# Switches.net
KiCad netlist of a schematic drawn in Altium Designer
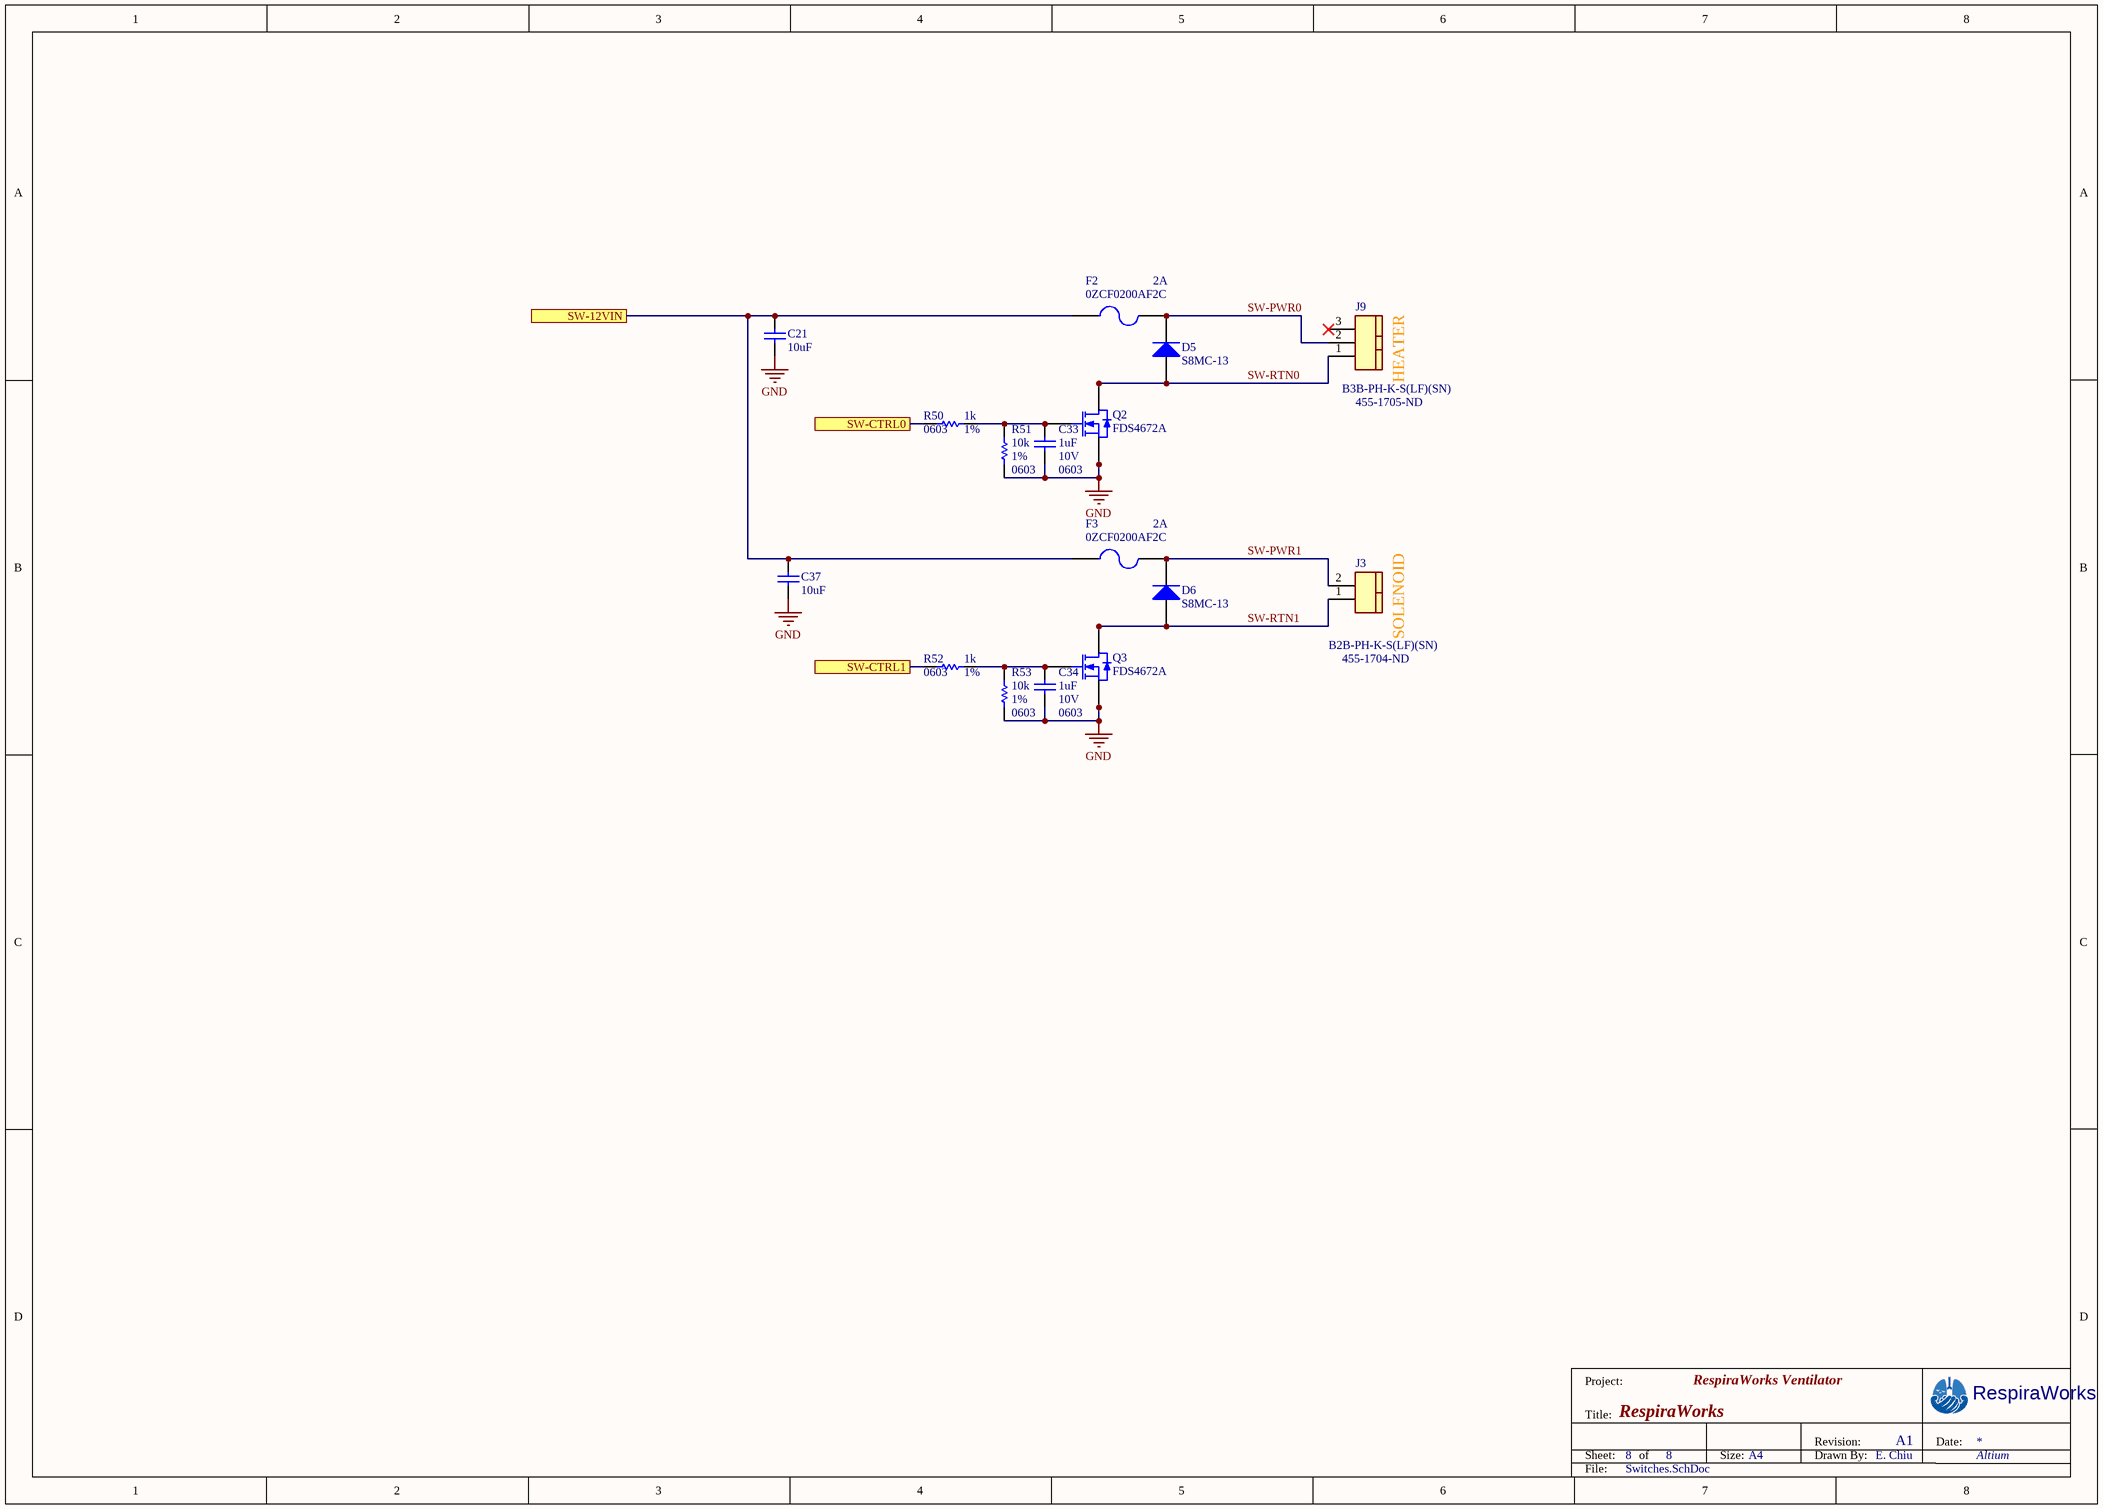
[diagram p0: Switches.SchDoc]

(export (version "E")
  (design (tool "Eeschema 10.0.6"))
  (components
    (comp (ref "C21")
      (value "10uF")
      (footprint "CAP1210")
      (description "Cap 1210")
      (fields (field (name "MANUFACTURER") "Murata") (field (name "VOLTAGE") "25V"))
      (libsource (lib "generic") (part "CAP 1210"))
    )
    (comp (ref "C33")
      (value "1uF")
      (footprint "CAP0603")
      (description "Cap 0603")
      (fields
        (field (name "MANUFACTURER") "Yageo")
        (field (name "VOLTAGE") "10V")
        (field (name "PCB PACKAGE") "0603")
        (field (name "Comment") "CAP 0603")
      )
      (libsource (lib "generic") (part "CAP 0603"))
    )
    (comp (ref "C34")
      (value "1uF")
      (footprint "CAP0603")
      (description "Cap 0603")
      (fields
        (field (name "MANUFACTURER") "Yageo")
        (field (name "VOLTAGE") "10V")
        (field (name "PCB PACKAGE") "0603")
        (field (name "Comment") "CAP 0603")
      )
      (libsource (lib "generic") (part "CAP 0603"))
    )
    (comp (ref "C37")
      (value "10uF")
      (footprint "CAP1210")
      (description "Cap 1210")
      (fields (field (name "MANUFACTURER") "Murata") (field (name "VOLTAGE") "25V"))
      (libsource (lib "generic") (part "CAP 1210"))
    )
    (comp (ref "D5")
      (value "S8MC-13")
      (footprint "DO-214AC")
      (description "Ultra-Fast Signal Diode, Silicon, 100V, 300mA")
      (fields (field (name "MANUFACTURER") "Diodes Inc.") (field (name "MANUFACTURER P/N") "S8MC-13"))
      (libsource (lib "diodes-inc") (part "S8MC-13"))
    )
    (comp (ref "D6")
      (value "S8MC-13")
      (footprint "DO-214AC")
      (description "Ultra-Fast Signal Diode, Silicon, 100V, 300mA")
      (fields (field (name "MANUFACTURER") "Diodes Inc.") (field (name "MANUFACTURER P/N") "S8MC-13"))
      (libsource (lib "diodes-inc") (part "S8MC-13"))
    )
    (comp (ref "F2")
      (value "0ZCF0200AF2C")
      (footprint "FUSE2920")
      (description "PTC Fuse, 2A Hold, 24V, 2920 size")
      (fields
        (field (name "MANUFACTURER P/N") "0ZCF0200AF2C")
        (field (name "MANUFACTURER") "Belfuse")
        (field (name "I(HOLD)") "2A")
      )
      (libsource (lib "belfuse") (part "0ZCF0200AF2C"))
    )
    (comp (ref "F3")
      (value "0ZCF0200AF2C")
      (footprint "FUSE2920")
      (description "PTC Fuse, 2A Hold, 24V, 2920 size")
      (fields
        (field (name "MANUFACTURER P/N") "0ZCF0200AF2C")
        (field (name "MANUFACTURER") "Belfuse")
        (field (name "I(HOLD)") "2A")
      )
      (libsource (lib "belfuse") (part "0ZCF0200AF2C"))
    )
    (comp (ref "J3")
      (value "B2B-PH-K-S(LF)(SN)")
      (footprint "JST_B2B-XH-AM")
      (description "CONN HEADER PH TOP 2POS 2MM")
      (fields
        (field (name "MANUFACTURER") "JST Sales America Inc.")
        (field (name "SUPPLIER PART NUMBER 1") "455-1704-ND")
      )
      (libsource (lib "JST XH") (part "B2B-PH-K-S(LF)(SN)"))
    )
    (comp (ref "J9")
      (value "B3B-PH-K-S(LF)(SN)")
      (footprint "JST_B3B-XH-AM")
      (description "CONN HEADER PH TOP 3POS 2MM")
      (fields
        (field (name "MANUFACTURER") "JST Sales America Inc.")
        (field (name "SUPPLIER PART NUMBER 1") "455-1705-ND")
      )
      (libsource (lib "JST XH") (part "B3B-PH-K-S(LF)(SN)"))
    )
    (comp (ref "Q2")
      (value "FDS4672A")
      (footprint "8-SOIC")
      (description "Transistor, BJT NPN, General Purpose 40V")
      (fields (field (name "MANUFACTURER") "On Semi") (field (name "MANUFACTURER P/N") "FDS4672A"))
      (libsource (lib "on-semi") (part "FDS4672A"))
    )
    (comp (ref "Q3")
      (value "FDS4672A")
      (footprint "8-SOIC")
      (description "Transistor, BJT NPN, General Purpose 40V")
      (fields (field (name "MANUFACTURER") "On Semi") (field (name "MANUFACTURER P/N") "FDS4672A"))
      (libsource (lib "on-semi") (part "FDS4672A"))
    )
    (comp (ref "R50")
      (value "1k")
      (footprint "RES0603")
      (description "Res 0603")
      (fields
        (field (name "MANUFACTURER") "Yageo")
        (field (name "PCB PACKAGE") "0603")
        (field (name "TOLERANCE") "1%")
        (field (name "Comment") "RES 0603")
      )
      (libsource (lib "generic") (part "RES 0603"))
    )
    (comp (ref "R51")
      (value "10k")
      (footprint "RES0603")
      (description "Res 0603")
      (fields
        (field (name "MANUFACTURER") "Yageo")
        (field (name "PCB PACKAGE") "0603")
        (field (name "TOLERANCE") "1%")
        (field (name "Comment") "RES 0603")
      )
      (libsource (lib "generic") (part "RES 0603"))
    )
    (comp (ref "R52")
      (value "1k")
      (footprint "RES0603")
      (description "Res 0603")
      (fields
        (field (name "MANUFACTURER") "Yageo")
        (field (name "PCB PACKAGE") "0603")
        (field (name "TOLERANCE") "1%")
        (field (name "Comment") "RES 0603")
      )
      (libsource (lib "generic") (part "RES 0603"))
    )
    (comp (ref "R53")
      (value "10k")
      (footprint "RES0603")
      (description "Res 0603")
      (fields
        (field (name "MANUFACTURER") "Yageo")
        (field (name "PCB PACKAGE") "0603")
        (field (name "TOLERANCE") "1%")
        (field (name "Comment") "RES 0603")
      )
      (libsource (lib "generic") (part "RES 0603"))
    )
  )
  (nets
    (net (code "1") (name "/SW-12VIN") (class "Default")
      (node (ref "C21") (pin "2") (pinfunction "2_2") (pintype "passive"))
      (node (ref "C37") (pin "2") (pinfunction "2_2") (pintype "passive"))
      (node (ref "F2") (pin "1") (pinfunction "1_1") (pintype "passive"))
      (node (ref "F3") (pin "1") (pinfunction "1_1") (pintype "passive"))
    )
    (net (code "2") (name "/SW-CTRL0") (class "Default")
      (node (ref "R50") (pin "2") (pinfunction "2_2") (pintype "passive"))
    )
    (net (code "3") (name "/SW-CTRL1") (class "Default")
      (node (ref "R52") (pin "2") (pinfunction "2_2") (pintype "passive"))
    )
    (net (code "4") (name "/SW-PWR0") (class "Default")
      (node (ref "D5") (pin "K") (pinfunction "K_K") (pintype "passive"))
      (node (ref "F2") (pin "2") (pinfunction "2_2") (pintype "passive"))
      (node (ref "J9") (pin "2") (pinfunction "2_2") (pintype "passive"))
    )
    (net (code "5") (name "/SW-PWR1") (class "Default")
      (node (ref "D6") (pin "K") (pinfunction "K_K") (pintype "passive"))
      (node (ref "F3") (pin "2") (pinfunction "2_2") (pintype "passive"))
      (node (ref "J3") (pin "2") (pinfunction "2_2") (pintype "passive"))
    )
    (net (code "6") (name "/SW-RTN0") (class "Default")
      (node (ref "D5") (pin "A") (pinfunction "A_A") (pintype "passive"))
      (node (ref "J9") (pin "1") (pinfunction "1_1") (pintype "passive"))
      (node (ref "Q2") (pin "5") (pinfunction "D_5") (pintype "passive"))
      (node (ref "Q2") (pin "6") (pinfunction "D_6") (pintype "passive"))
      (node (ref "Q2") (pin "7") (pinfunction "D_7") (pintype "passive"))
      (node (ref "Q2") (pin "8") (pinfunction "D_8") (pintype "passive"))
    )
    (net (code "7") (name "/SW-RTN1") (class "Default")
      (node (ref "D6") (pin "A") (pinfunction "A_A") (pintype "passive"))
      (node (ref "J3") (pin "1") (pinfunction "1_1") (pintype "passive"))
      (node (ref "Q3") (pin "5") (pinfunction "D_5") (pintype "passive"))
      (node (ref "Q3") (pin "6") (pinfunction "D_6") (pintype "passive"))
      (node (ref "Q3") (pin "7") (pinfunction "D_7") (pintype "passive"))
      (node (ref "Q3") (pin "8") (pinfunction "D_8") (pintype "passive"))
    )
    (net (code "8") (name "GND") (class "Default")
      (node (ref "C21") (pin "1") (pinfunction "1_1") (pintype "passive"))
      (node (ref "C33") (pin "2") (pinfunction "2_2") (pintype "passive"))
      (node (ref "C34") (pin "2") (pinfunction "2_2") (pintype "passive"))
      (node (ref "C37") (pin "1") (pinfunction "1_1") (pintype "passive"))
      (node (ref "Q2") (pin "1") (pinfunction "S_1") (pintype "passive"))
      (node (ref "Q2") (pin "2") (pinfunction "S_2") (pintype "passive"))
      (node (ref "Q2") (pin "3") (pinfunction "S_3") (pintype "passive"))
      (node (ref "Q3") (pin "1") (pinfunction "S_1") (pintype "passive"))
      (node (ref "Q3") (pin "2") (pinfunction "S_2") (pintype "passive"))
      (node (ref "Q3") (pin "3") (pinfunction "S_3") (pintype "passive"))
      (node (ref "R51") (pin "2") (pinfunction "2_2") (pintype "passive"))
      (node (ref "R53") (pin "2") (pinfunction "2_2") (pintype "passive"))
    )
    (net (code "9") (name "Net-(Q2-G)") (class "Default")
      (node (ref "C33") (pin "1") (pinfunction "1_1") (pintype "passive"))
      (node (ref "Q2") (pin "4") (pinfunction "G_4") (pintype "passive"))
      (node (ref "R50") (pin "1") (pinfunction "1_1") (pintype "passive"))
      (node (ref "R51") (pin "1") (pinfunction "1_1") (pintype "passive"))
    )
    (net (code "10") (name "Net-(Q3-G)") (class "Default")
      (node (ref "C34") (pin "1") (pinfunction "1_1") (pintype "passive"))
      (node (ref "Q3") (pin "4") (pinfunction "G_4") (pintype "passive"))
      (node (ref "R52") (pin "1") (pinfunction "1_1") (pintype "passive"))
      (node (ref "R53") (pin "1") (pinfunction "1_1") (pintype "passive"))
    )
    (net (code "11") (name "unconnected-(J9-Pad3)") (class "Default")
      (node (ref "J9") (pin "3") (pinfunction "3_3") (pintype "passive+no_connect"))
    )
  )
)
